# FanControl.net
KiCad netlist of a schematic drawn in Altium Designer
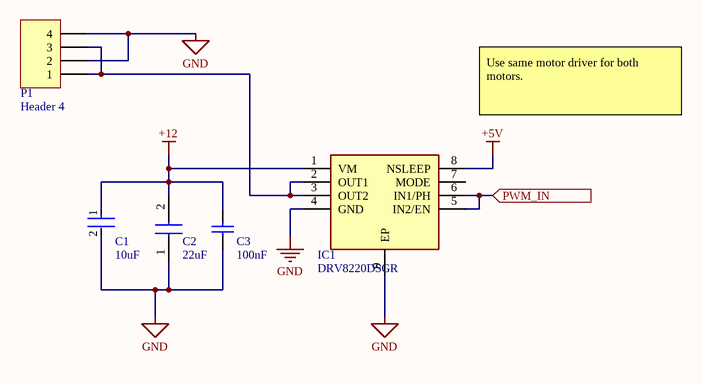
[diagram p0: FanControl.SchDoc]

(export (version "E")
  (design (tool "Eeschema 10.0.6"))
  (components
    (comp (ref "C1")
      (value "CL05A106MP5NUNC")
      (footprint "FP-CL05A106MP5NUNC-MFG")
      (description "CAP CER 10UF 10V X5R 0402")
      (fields
        (field (name "OCTOPART") "https://octopart.com/cl05a106mp5nunc-samsung-22457395")
        (field (name "TOLERANCE") "20%")
        (field (name "CAPACITANCE") "10uF")
      )
      (libsource (lib "Altium Content Vault") (part "b4654b650e69147ec39a6b967a45e02"))
    )
    (comp (ref "C2")
      (value "22uF")
      (footprint "SamacSys:CAPC1608X105N")
      (description "Capacitor")
      (fields
        (field (name "MANUFACTURER_PART_NUMBER") "CL10A226MP8NUNE")
        (field (name "MOUSER PART NUMBER") "187-CL10A226MP8NUNE")
      )
      (libsource (lib "*") (part "CL10A226MP8NUNE"))
    )
    (comp (ref "C3")
      (value "CL05B104KO5NNNC")
      (footprint "CAPC1050X55X23ML05T13")
      (description "Chip Capacitor, 100 nF, +/- 10%, 16 V, -55 to 125 degC, 0402 (1005 Metric), RoHS, Tape and Reel")
      (fields (field (name "MANUFACTURER") "Samsung Electro-Mechanics") (field (name "CAPACITANCE") "100nF"))
      (libsource (lib "Altium Content Vault") (part "CAP-NP-2"))
    )
    (comp (ref "IC1")
      (value "DRV8220DSGR")
      (footprint "SamacSys:SON50P200X200X80-9N")
      (description "Integrated Circuit")
      (fields (field (name "MOUSER PART NUMBER") "595-DRV8220DSGR"))
      (libsource (lib "SamacSys") (part "DRV8220DSGR"))
    )
    (comp (ref "P1")
      (value "Header 4")
      (footprint "HDR1X4")
      (description "Header, 4-Pin")
      (fields (field (name "PUBLISHER") "Altium Limited"))
      (libsource (lib "Miscellaneous Connectors") (part "Header 4"))
    )
  )
  (nets
    (net (code "1") (name "+5V") (class "Default")
      (node (ref "IC1") (pin "8") (pinfunction "NSLEEP_8") (pintype "passive"))
    )
    (net (code "2") (name "+12") (class "Default")
      (node (ref "C1") (pin "1") (pinfunction "1_1") (pintype "passive"))
      (node (ref "C2") (pin "2") (pinfunction "2_2") (pintype "passive"))
      (node (ref "C3") (pin "2") (pinfunction "2_2") (pintype "passive"))
      (node (ref "IC1") (pin "1") (pinfunction "VM_1") (pintype "passive"))
    )
    (net (code "3") (name "/PWM_IN") (class "Default")
      (node (ref "IC1") (pin "5") (pinfunction "IN2/EN_5") (pintype "passive"))
      (node (ref "IC1") (pin "6") (pinfunction "IN1/PH_6") (pintype "passive"))
    )
    (net (code "4") (name "GND") (class "Default")
      (node (ref "C1") (pin "2") (pinfunction "2_2") (pintype "passive"))
      (node (ref "C2") (pin "1") (pinfunction "1_1") (pintype "passive"))
      (node (ref "C3") (pin "1") (pinfunction "1_1") (pintype "passive"))
      (node (ref "IC1") (pin "4") (pinfunction "GND_4") (pintype "passive"))
      (node (ref "IC1") (pin "9") (pinfunction "EP_9") (pintype "passive"))
      (node (ref "P1") (pin "2") (pinfunction "2_2") (pintype "passive"))
      (node (ref "P1") (pin "4") (pinfunction "4_4") (pintype "passive"))
    )
    (net (code "5") (name "Net-(IC1-OUT1)") (class "Default")
      (node (ref "IC1") (pin "2") (pinfunction "OUT1_2") (pintype "passive"))
      (node (ref "IC1") (pin "3") (pinfunction "OUT2_3") (pintype "passive"))
      (node (ref "P1") (pin "1") (pinfunction "1_1") (pintype "passive"))
      (node (ref "P1") (pin "3") (pinfunction "3_3") (pintype "passive"))
    )
    (net (code "6") (name "unconnected-(IC1-MODE-Pad7)") (class "Default")
      (node (ref "IC1") (pin "7") (pinfunction "MODE_7") (pintype "passive"))
    )
  )
)
